# 04_POWER.net
KiCad netlist of a schematic drawn in Altium Designer
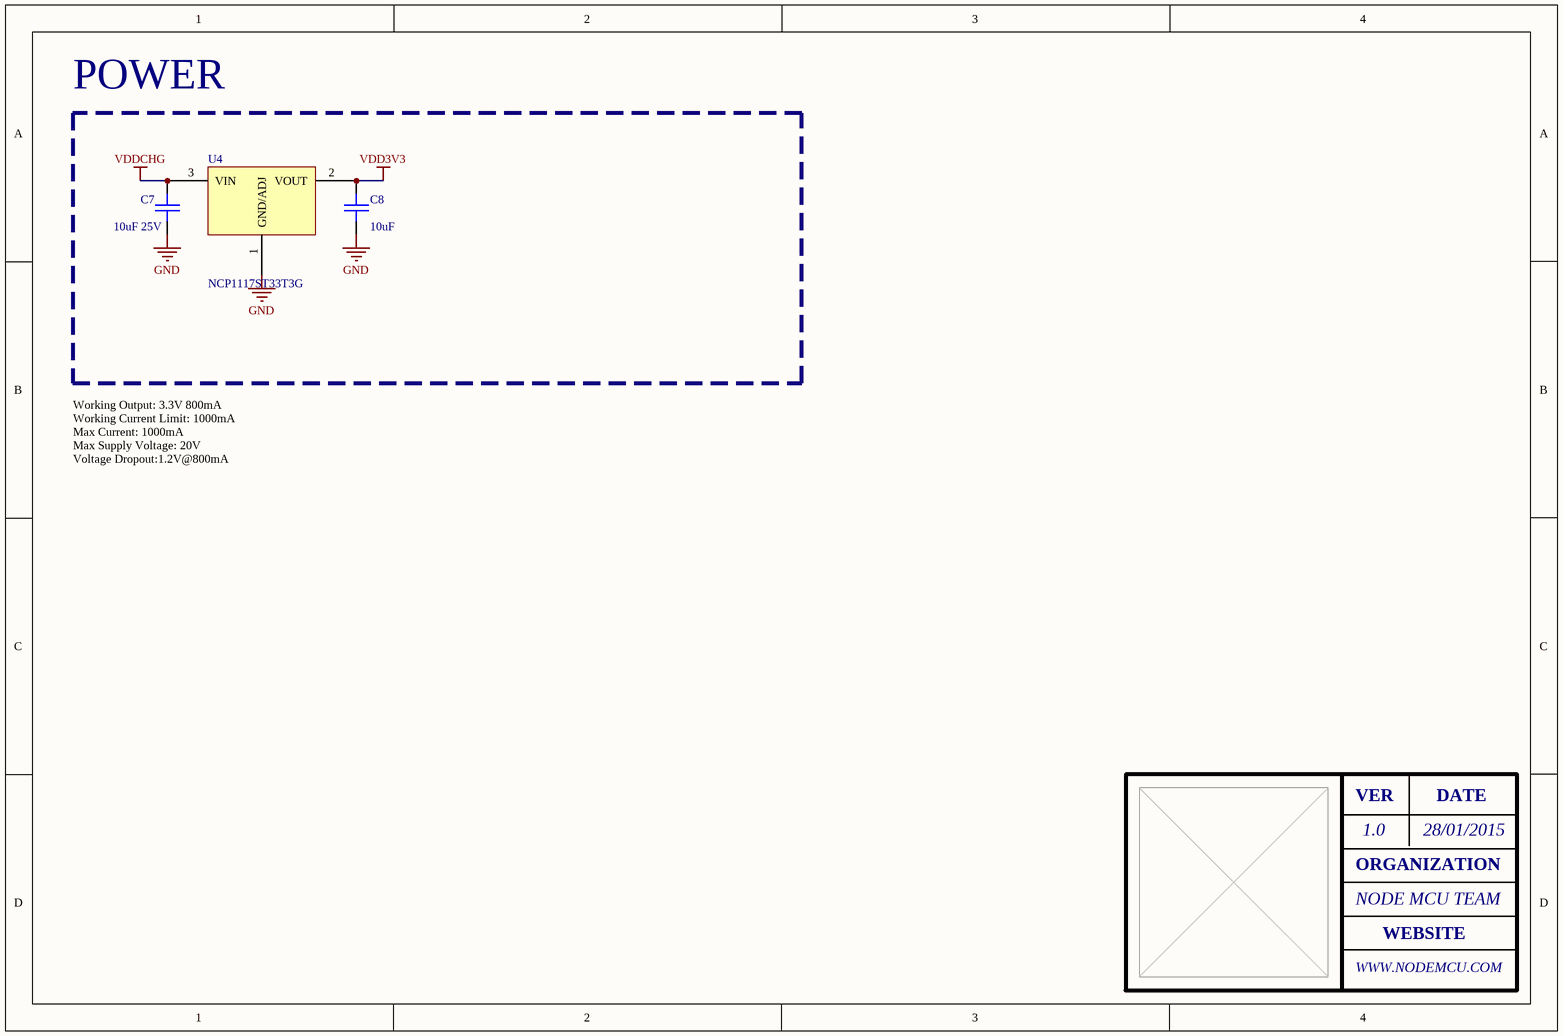
[diagram p0: 04_POWER.SchDoc]

(export (version "E")
  (design (tool "Eeschema 10.0.6"))
  (components
    (comp (ref "C7")
      (value "10uF 25V")
      (footprint "SMT_C_0805")
      (description "Surface mount capacitor 0805")
      (libsource (lib "cupmat") (part "SMT_C_0805"))
    )
    (comp (ref "C8")
      (value "10uF")
      (footprint "SMT_C_0402")
      (description "Surface mount capacitor 0402")
      (libsource (lib "cupmat") (part "SMT_C_0402"))
    )
    (comp (ref "U4")
      (value "NCP1117ST33T3G")
      (footprint "SOT-223")
      (description "NCP1117, NCV1117. 1.0 A Low-Dropout Positive  Fixed and Adjustable  Voltage Regulators")
      (libsource (lib "cupmat") (part "NCP1117"))
    )
  )
  (nets
    (net (code "1") (name "GND") (class "Default")
      (node (ref "C7") (pin "2") (pinfunction "2_2") (pintype "passive"))
      (node (ref "C8") (pin "2") (pinfunction "2_2") (pintype "passive"))
      (node (ref "U4") (pin "1") (pinfunction "GND/ADJ_1") (pintype "passive"))
    )
    (net (code "2") (name "VDD3V3") (class "Default")
      (node (ref "C8") (pin "1") (pinfunction "1_1") (pintype "passive"))
      (node (ref "U4") (pin "2") (pinfunction "VOUT_2") (pintype "passive"))
    )
    (net (code "3") (name "VDDCHG") (class "Default")
      (node (ref "C7") (pin "1") (pinfunction "1_1") (pintype "passive"))
      (node (ref "U4") (pin "3") (pinfunction "VIN_3") (pintype "passive"))
    )
  )
)
